# SimpleFOCShield_v3-Redesigned.net
KiCad netlist of a schematic drawn in EasyEDA Pro
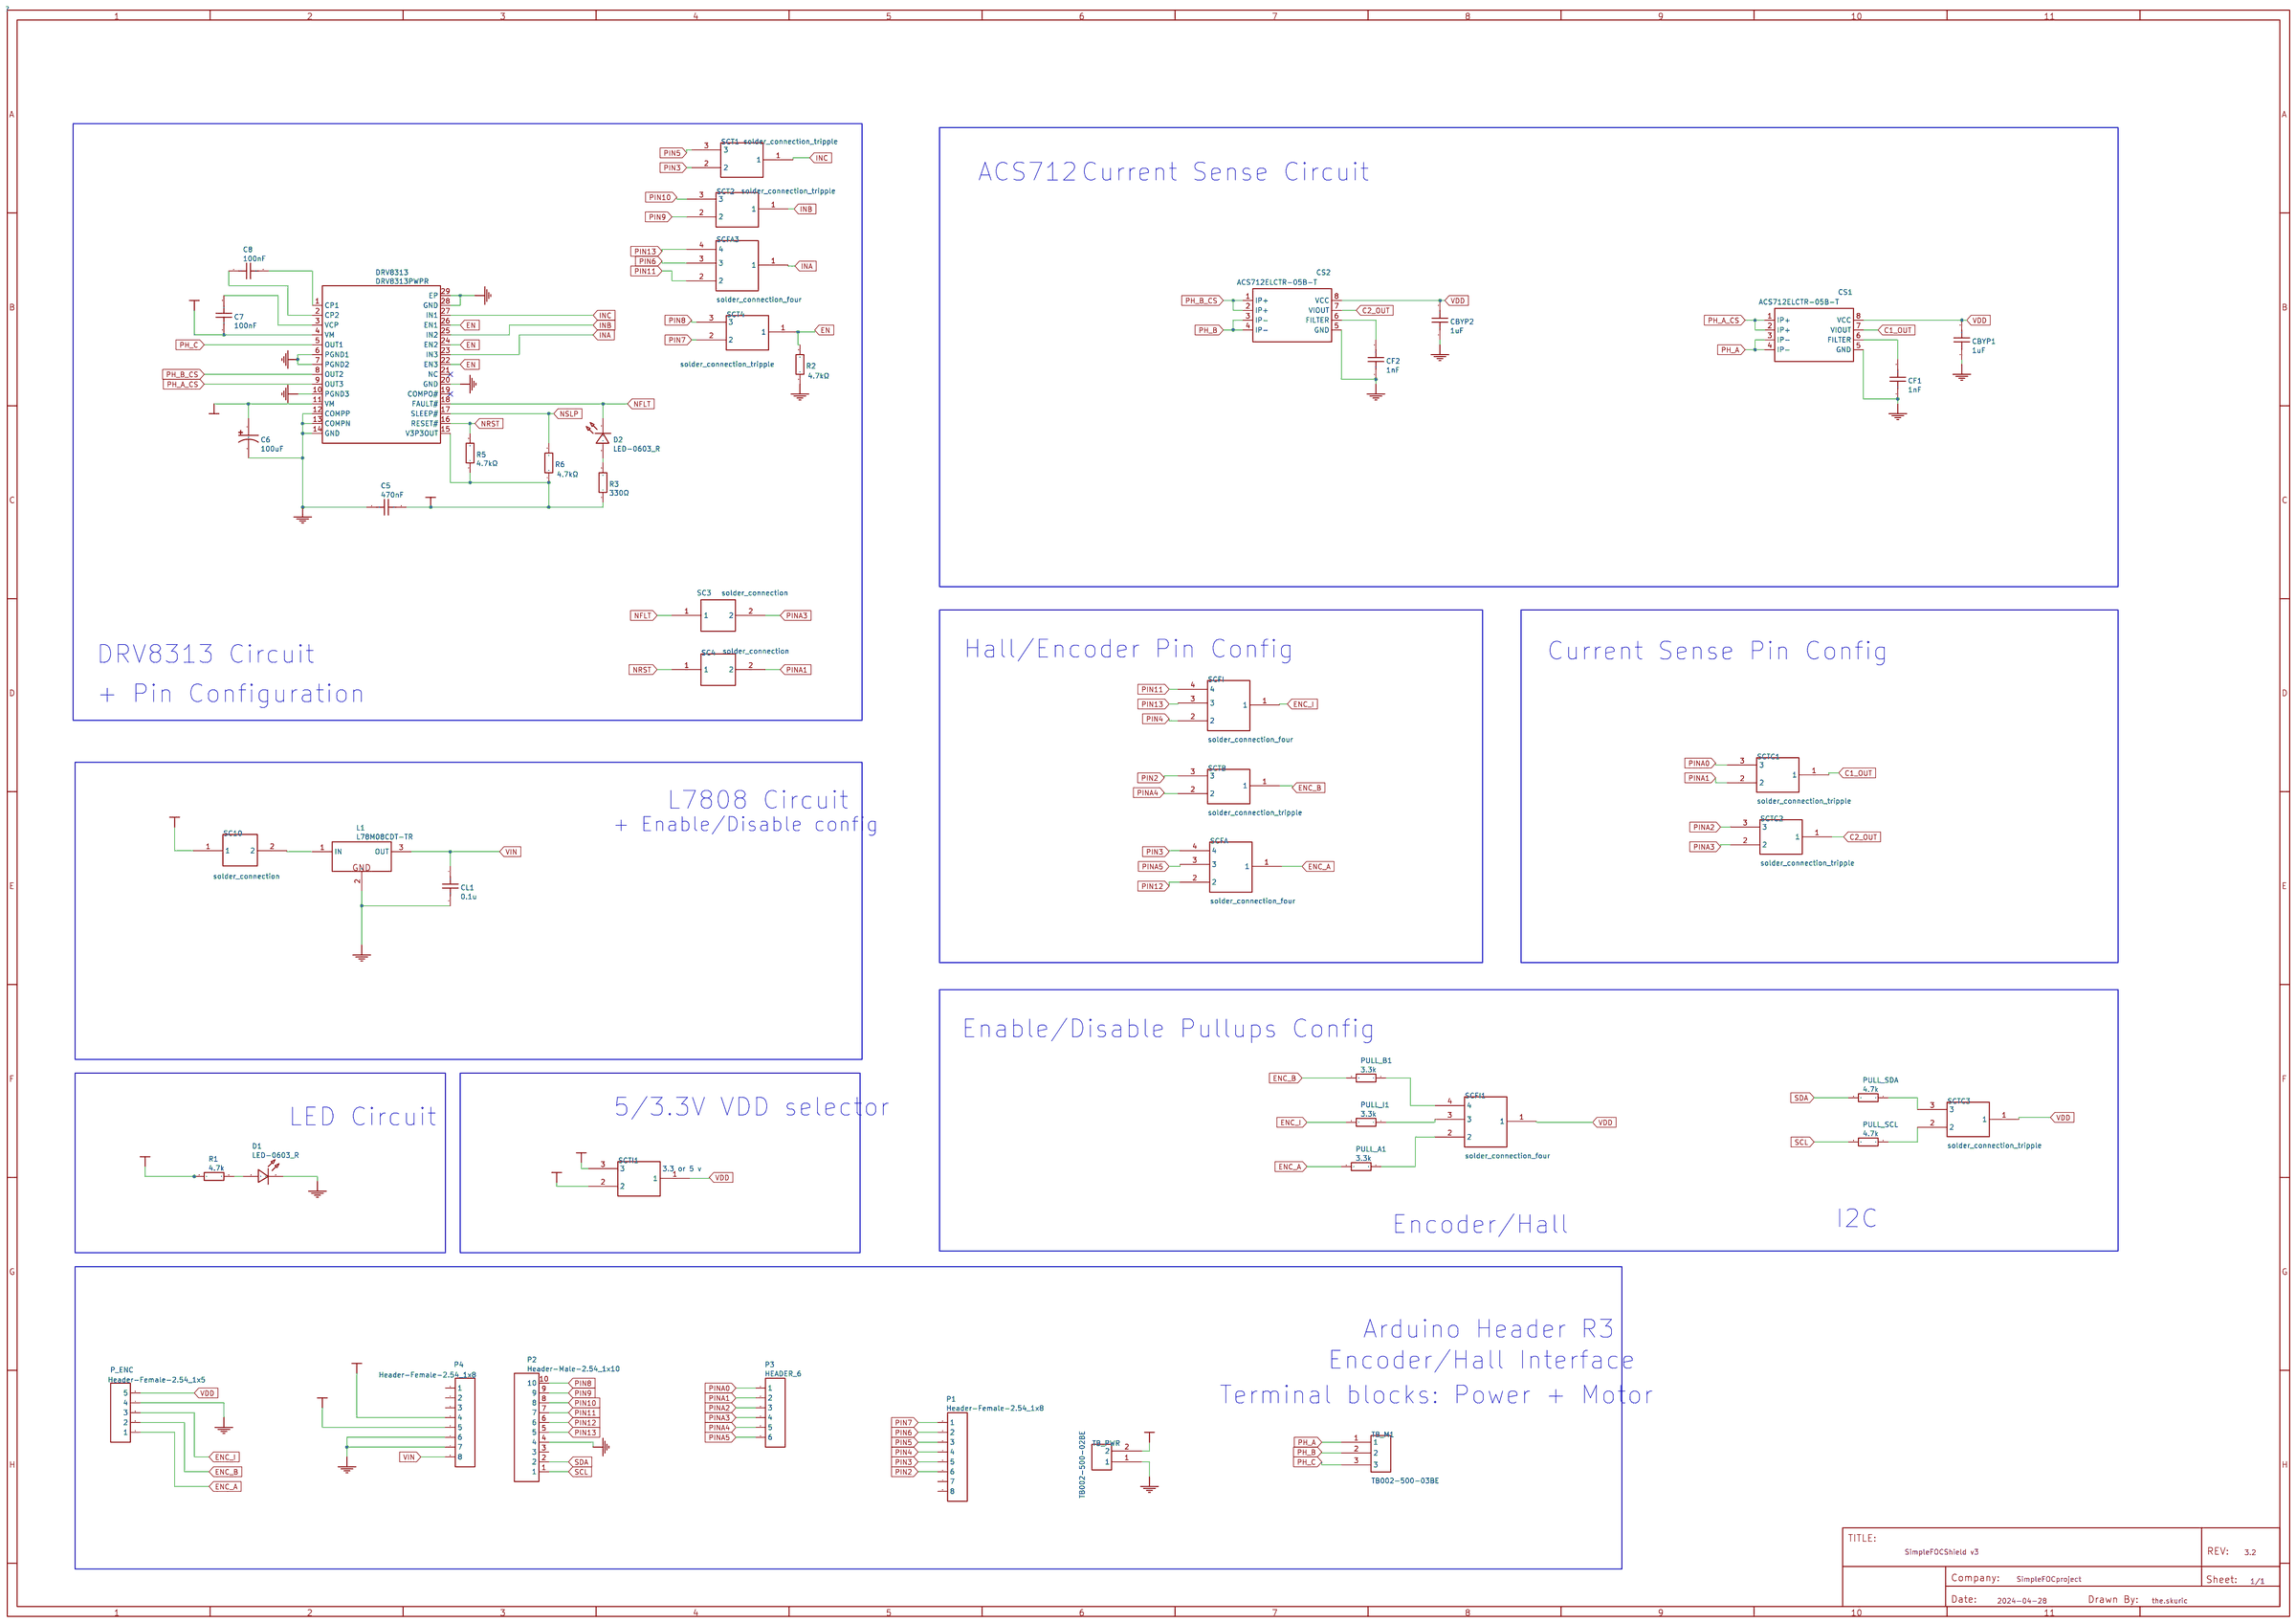
[diagram p0: schematic sheet]

(export (version "E")
  (design (tool "Eeschema 10.0.6"))
  (components
    (comp (ref "C5")
      (value "470nF")
      (footprint "easyedapro:C0603_1")
      (fields (field (name "Manufacturer Part") "CC0603ZRY5V6BB474") (field (name "Manufacturer") "YAGEO"))
      (libsource (lib "easyedapro") (part "470nF"))
    )
    (comp (ref "C6")
      (value "100uF")
      (footprint "easyedapro:CAP-SMD_BD6.3-L6.6-W6.6-FD")
      (fields
        (field (name "Manufacturer Part") "VT1V101M-CRE77")
        (field (name "Manufacturer") "Vertical Technology")
      )
      (libsource (lib "easyedapro") (part "100uF"))
    )
    (comp (ref "C7")
      (value "100nF")
      (footprint "easyedapro:C0603_1")
      (fields (field (name "Manufacturer Part") "CL10B104KB8NNNC") (field (name "Manufacturer") "SAMSUNG"))
      (libsource (lib "easyedapro") (part "100nF"))
    )
    (comp (ref "C8")
      (value "100nF")
      (footprint "easyedapro:C0603_1")
      (fields (field (name "Manufacturer Part") "CL10B104KB8NNNC") (field (name "Manufacturer") "SAMSUNG"))
      (libsource (lib "easyedapro") (part "100nF"))
    )
    (comp (ref "CBYP1")
      (value "1uF")
      (footprint "easyedapro:C0603_1")
      (libsource (lib "easyedapro") (part "1uF"))
    )
    (comp (ref "CBYP2")
      (value "1uF")
      (footprint "easyedapro:C0603_1")
      (libsource (lib "easyedapro") (part "1uF"))
    )
    (comp (ref "CF1")
      (value "1nF")
      (footprint "easyedapro:C0603_1")
      (libsource (lib "easyedapro") (part "1nF"))
    )
    (comp (ref "CF2")
      (value "1nF")
      (footprint "easyedapro:C0603_1")
      (libsource (lib "easyedapro") (part "1nF"))
    )
    (comp (ref "CL1")
      (value "0.1u")
      (footprint "easyedapro:C0603_1")
      (libsource (lib "easyedapro") (part "0.1u"))
    )
    (comp (ref "CS1")
      (value "ACS712ELCTR-05B-T")
      (footprint "easyedapro:SOIC-8_L5.0-W4.0-P1.27-LS6.0-BL")
      (fields (field (name "Manufacturer") "ALLEGRO(美国埃戈罗)"))
      (libsource (lib "easyedapro") (part "ACS712ELCTR-05B-T"))
    )
    (comp (ref "CS2")
      (value "ACS712ELCTR-05B-T")
      (footprint "easyedapro:SOIC-8_L5.0-W4.0-P1.27-LS6.0-BL")
      (fields (field (name "Manufacturer") "ALLEGRO(美国埃戈罗)"))
      (libsource (lib "easyedapro") (part "ACS712ELCTR-05B-T"))
    )
    (comp (ref "D1")
      (value "LED-0603_R")
      (footprint "easyedapro:LED0603_RED")
      (fields
        (field (name "Manufacturer Part") "19-217/R6C-AL1M2VY/3T")
        (field (name "Manufacturer") "EVERLIGHT(台湾亿光)")
      )
      (libsource (lib "easyedapro") (part "LED-0603_R"))
    )
    (comp (ref "D2")
      (value "LED-0603_R")
      (footprint "easyedapro:LED0603_RED")
      (fields
        (field (name "Manufacturer Part") "19-217/R6C-AL1M2VY/3T")
        (field (name "Manufacturer") "EVERLIGHT(台湾亿光)")
      )
      (libsource (lib "easyedapro") (part "LED-0603_R"))
    )
    (comp (ref "DRV8313")
      (value "DRV8313PWPR")
      (footprint "easyedapro:HTSSOP-28_L9.8-W4.5-P0.65-LS6.6-BL-EP")
      (fields (field (name "Manufacturer") "Texas Instruments"))
      (libsource (lib "easyedapro") (part "DRV8313PWPR"))
    )
    (comp (ref "L1")
      (value "L78M08CDT-TR")
      (footprint "easyedapro:TO-252-2_L6.6-W6.1-P4.57-LS9.9-TL-CW")
      (fields (field (name "Manufacturer") "STMicroelectronics"))
      (libsource (lib "easyedapro") (part "L78M08CDT-TR"))
    )
    (comp (ref "P1")
      (value "Header-Female-2.54_1x8")
      (footprint "easyedapro:HDR-TH_8P-P2.54-V-F-1")
      (fields
        (field (name "Manufacturer Part") "Female headerHDR1X8-2.54")
        (field (name "Manufacturer") "BOOMELE")
      )
      (libsource (lib "easyedapro") (part "Header-Female-2.54_1x8"))
    )
    (comp (ref "P2")
      (value "Header-Male-2.54_1x10")
      (footprint "easyedapro:HDR-TH_10P-P2.54-V-M-1")
      (fields (field (name "Manufacturer Part") "Headers  Pins2.54mm1*10P"))
      (libsource (lib "easyedapro") (part "Header-Male-2.54_1x10"))
    )
    (comp (ref "P3")
      (value "HEADER_6")
      (footprint "easyedapro:HDR-M-2.54_1X6")
      (libsource (lib "easyedapro") (part "HEADER_6"))
    )
    (comp (ref "P4")
      (value "Header-Female-2.54_1x8")
      (footprint "easyedapro:HDR-TH_8P-P2.54-V-F-1")
      (fields
        (field (name "Manufacturer Part") "Female headerHDR1X8-2.54")
        (field (name "Manufacturer") "BOOMELE")
      )
      (libsource (lib "easyedapro") (part "Header-Female-2.54_1x8"))
    )
    (comp (ref "PULL_A1")
      (value "3.3k")
      (footprint "easyedapro:R0603_1")
      (libsource (lib "easyedapro") (part "3.3k"))
    )
    (comp (ref "PULL_B1")
      (value "3.3k")
      (footprint "easyedapro:R0603_1")
      (libsource (lib "easyedapro") (part "3.3k"))
    )
    (comp (ref "PULL_I1")
      (value "3.3k")
      (footprint "easyedapro:R0603_1")
      (libsource (lib "easyedapro") (part "3.3k"))
    )
    (comp (ref "PULL_SCL")
      (value "4.7k")
      (footprint "easyedapro:R0603_1")
      (fields (field (name "Manufacturer Part") "0603WAF4701T5E") (field (name "Manufacturer") "UniOhm"))
      (libsource (lib "easyedapro") (part "4.7k"))
    )
    (comp (ref "PULL_SDA")
      (value "4.7k")
      (footprint "easyedapro:R0603_1")
      (fields (field (name "Manufacturer Part") "0603WAF4701T5E") (field (name "Manufacturer") "UniOhm"))
      (libsource (lib "easyedapro") (part "4.7k"))
    )
    (comp (ref "P_ENC")
      (value "Header-Female-2.54_1x5")
      (footprint "easyedapro:HDR-TH_5P-P2.54-V-F")
      (fields
        (field (name "Manufacturer Part") "2.54mm 1*5p Female header")
        (field (name "Manufacturer") "BOOMELE")
      )
      (libsource (lib "easyedapro") (part "Header-Female-2.54_1x5"))
    )
    (comp (ref "R1")
      (value "4.7k")
      (footprint "easyedapro:R0603_1")
      (fields (field (name "Manufacturer Part") "0603WAF4701T5E") (field (name "Manufacturer") "UniOhm"))
      (libsource (lib "easyedapro") (part "4.7k"))
    )
    (comp (ref "R2")
      (value "4.7kΩ")
      (footprint "easyedapro:R0603_1")
      (fields (field (name "Manufacturer Part") "0603WAF4701T5E") (field (name "Manufacturer") "UniOhm"))
      (libsource (lib "easyedapro") (part "4.7kΩ"))
    )
    (comp (ref "R3")
      (value "330Ω")
      (footprint "easyedapro:R0603_1")
      (libsource (lib "easyedapro") (part "330Ω"))
    )
    (comp (ref "R5")
      (value "4.7kΩ")
      (footprint "easyedapro:R0603_1")
      (fields (field (name "Manufacturer Part") "0603WAF4701T5E") (field (name "Manufacturer") "UniOhm"))
      (libsource (lib "easyedapro") (part "4.7kΩ"))
    )
    (comp (ref "R6")
      (value "4.7kΩ")
      (footprint "easyedapro:R0603_1")
      (fields (field (name "Manufacturer Part") "0603WAF4701T5E") (field (name "Manufacturer") "UniOhm"))
      (libsource (lib "easyedapro") (part "4.7kΩ"))
    )
    (comp (ref "SC3")
      (value "solder_connection")
      (footprint "easyedapro:SOLDER_CONNECTION")
      (libsource (lib "easyedapro") (part "solder_connection"))
    )
    (comp (ref "SC4")
      (value "solder_connection")
      (footprint "easyedapro:SOLDER_CONNECTION")
      (libsource (lib "easyedapro") (part "solder_connection"))
    )
    (comp (ref "SC10")
      (value "solder_connection")
      (footprint "easyedapro:SOLDER_CONNECTION")
      (libsource (lib "") (part "solder_connection_1"))
    )
    (comp (ref "SCFA")
      (value "solder_connection_four")
      (footprint "easyedapro:SOLDER_CONNECTION_FOUR")
      (libsource (lib "") (part "solder_connection_four_1"))
    )
    (comp (ref "SCFA3")
      (value "solder_connection_four")
      (footprint "easyedapro:SOLDER_CONNECTION_FOUR")
      (libsource (lib "") (part "solder_connection_four_2"))
    )
    (comp (ref "SCFI")
      (value "solder_connection_four")
      (footprint "easyedapro:SOLDER_CONNECTION_FOUR")
      (libsource (lib "easyedapro") (part "solder_connection_four"))
    )
    (comp (ref "SCFI1")
      (value "solder_connection_four")
      (footprint "easyedapro:SOLDER_CONNECTION_FOUR")
      (libsource (lib "easyedapro") (part "solder_connection_four"))
    )
    (comp (ref "SCT1")
      (value "solder_connection_tripple")
      (footprint "easyedapro:SOLDER_CONNECTION_TRIPPLE")
      (libsource (lib "") (part "solder_connection_tripple_5"))
    )
    (comp (ref "SCT2")
      (value "solder_connection_tripple")
      (footprint "easyedapro:SOLDER_CONNECTION_TRIPPLE")
      (libsource (lib "") (part "solder_connection_tripple_1"))
    )
    (comp (ref "SCT4")
      (value "solder_connection_tripple")
      (footprint "easyedapro:SOLDER_CONNECTION_TRIPPLE")
      (libsource (lib "") (part "solder_connection_tripple_4"))
    )
    (comp (ref "SCTB")
      (value "solder_connection_tripple")
      (footprint "easyedapro:SOLDER_CONNECTION_TRIPPLE")
      (libsource (lib "") (part "solder_connection_tripple_3"))
    )
    (comp (ref "SCTC1")
      (value "solder_connection_tripple")
      (footprint "easyedapro:SOLDER_CONNECTION_TRIPPLE")
      (libsource (lib "") (part "solder_connection_tripple_2"))
    )
    (comp (ref "SCTC2")
      (value "solder_connection_tripple")
      (footprint "easyedapro:SOLDER_CONNECTION_TRIPPLE")
      (libsource (lib "easyedapro") (part "solder_connection_tripple"))
    )
    (comp (ref "SCTC3")
      (value "solder_connection_tripple")
      (footprint "easyedapro:SOLDER_CONNECTION_TRIPPLE")
      (libsource (lib "easyedapro") (part "solder_connection_tripple"))
    )
    (comp (ref "SCTI1")
      (value "3.3 or 5 v")
      (footprint "easyedapro:SOLDER_CONNECTION_TRIPPLE")
      (libsource (lib "easyedapro") (part "3.3 or 5 v"))
    )
    (comp (ref "TB_M1")
      (value "TB002-500-03BE")
      (footprint "easyedapro:TB002-500-03BE")
      (libsource (lib "easyedapro") (part "TB002-500-03BE"))
    )
    (comp (ref "TB_PWR")
      (value "TB002-500-02BE")
      (footprint "easyedapro:TB002-500-02BE")
      (libsource (lib "easyedapro") (part "TB002-500-02BE"))
    )
  )
  (nets
    (net (code "1") (name "+5V") (class "Default")
      (node (ref "P4") (pin "5") (pinfunction "5_5") (pintype "input"))
      (node (ref "SCTI1") (pin "2") (pinfunction "2_2") (pintype "unspecified"))
    )
    (net (code "2") (name "3.3V") (class "Default")
      (node (ref "C5") (pin "2") (pinfunction "2_2") (pintype "unspecified"))
      (node (ref "DRV8313") (pin "15") (pinfunction "V3P3OUT_15") (pintype "unspecified"))
      (node (ref "R3") (pin "1") (pinfunction "1_1") (pintype "input"))
      (node (ref "R5") (pin "1") (pinfunction "1_1") (pintype "input"))
      (node (ref "R6") (pin "1") (pinfunction "1_1") (pintype "input"))
    )
    (net (code "3") (name "C1_OUT") (class "Default")
      (node (ref "CS1") (pin "7") (pinfunction "VIOUT_7") (pintype "unspecified"))
      (node (ref "SCTC1") (pin "1") (pinfunction "1_1") (pintype "unspecified"))
    )
    (net (code "4") (name "C2_OUT") (class "Default")
      (node (ref "CS2") (pin "7") (pinfunction "VIOUT_7") (pintype "unspecified"))
      (node (ref "SCTC2") (pin "1") (pinfunction "1_1") (pintype "unspecified"))
    )
    (net (code "5") (name "EN") (class "Default")
      (node (ref "DRV8313") (pin "22") (pinfunction "EN3_22") (pintype "unspecified"))
      (node (ref "DRV8313") (pin "24") (pinfunction "EN2_24") (pintype "unspecified"))
      (node (ref "DRV8313") (pin "26") (pinfunction "EN1_26") (pintype "unspecified"))
      (node (ref "R2") (pin "2") (pinfunction "2_2") (pintype "input"))
      (node (ref "SCT4") (pin "1") (pinfunction "1_1") (pintype "unspecified"))
    )
    (net (code "6") (name "ENC_A") (class "Default")
      (node (ref "PULL_A1") (pin "2") (pinfunction "2_2") (pintype "input"))
      (node (ref "P_ENC") (pin "1") (pinfunction "1_1") (pintype "input"))
      (node (ref "SCFA") (pin "1") (pinfunction "1_1") (pintype "unspecified"))
    )
    (net (code "7") (name "ENC_B") (class "Default")
      (node (ref "PULL_B1") (pin "2") (pinfunction "2_2") (pintype "input"))
      (node (ref "P_ENC") (pin "2") (pinfunction "2_2") (pintype "input"))
      (node (ref "SCTB") (pin "1") (pinfunction "1_1") (pintype "unspecified"))
    )
    (net (code "8") (name "ENC_I") (class "Default")
      (node (ref "PULL_I1") (pin "2") (pinfunction "2_2") (pintype "input"))
      (node (ref "P_ENC") (pin "3") (pinfunction "3_3") (pintype "input"))
      (node (ref "SCFI") (pin "1") (pinfunction "1_1") (pintype "unspecified"))
    )
    (net (code "9") (name "GND") (class "Default")
      (node (ref "C5") (pin "1") (pinfunction "1_1") (pintype "unspecified"))
      (node (ref "C6") (pin "2") (pinfunction "2_2") (pintype "unspecified"))
      (node (ref "CBYP1") (pin "1") (pinfunction "1_1") (pintype "unspecified"))
      (node (ref "CBYP2") (pin "1") (pinfunction "1_1") (pintype "unspecified"))
      (node (ref "CF1") (pin "1") (pinfunction "1_1") (pintype "unspecified"))
      (node (ref "CF2") (pin "1") (pinfunction "1_1") (pintype "unspecified"))
      (node (ref "CL1") (pin "2") (pinfunction "2_2") (pintype "unspecified"))
      (node (ref "CS1") (pin "5") (pinfunction "GND_5") (pintype "unspecified"))
      (node (ref "CS2") (pin "5") (pinfunction "GND_5") (pintype "unspecified"))
      (node (ref "D1") (pin "2") (pinfunction "2_2") (pintype "unspecified"))
      (node (ref "DRV8313") (pin "10") (pinfunction "PGND3_10") (pintype "unspecified"))
      (node (ref "DRV8313") (pin "12") (pinfunction "COMPP_12") (pintype "unspecified"))
      (node (ref "DRV8313") (pin "13") (pinfunction "COMPN_13") (pintype "unspecified"))
      (node (ref "DRV8313") (pin "14") (pinfunction "GND_14") (pintype "unspecified"))
      (node (ref "DRV8313") (pin "20") (pinfunction "GND_20") (pintype "unspecified"))
      (node (ref "DRV8313") (pin "28") (pinfunction "GND_28") (pintype "unspecified"))
      (node (ref "DRV8313") (pin "29") (pinfunction "EP_29") (pintype "unspecified"))
      (node (ref "DRV8313") (pin "6") (pinfunction "PGND1_6") (pintype "unspecified"))
      (node (ref "DRV8313") (pin "7") (pinfunction "PGND2_7") (pintype "unspecified"))
      (node (ref "L1") (pin "2") (pinfunction "GND_2") (pintype "unspecified"))
      (node (ref "P2") (pin "4") (pinfunction "4_4") (pintype "unspecified"))
      (node (ref "P4") (pin "6") (pinfunction "6_6") (pintype "input"))
      (node (ref "P4") (pin "7") (pinfunction "7_7") (pintype "input"))
      (node (ref "P_ENC") (pin "4") (pinfunction "4_4") (pintype "input"))
      (node (ref "R2") (pin "1") (pinfunction "1_1") (pintype "input"))
      (node (ref "TB_PWR") (pin "1") (pinfunction "1_1") (pintype "unspecified"))
    )
    (net (code "10") (name "INA") (class "Default")
      (node (ref "DRV8313") (pin "23") (pinfunction "IN3_23") (pintype "unspecified"))
      (node (ref "SCFA3") (pin "1") (pinfunction "1_1") (pintype "unspecified"))
    )
    (net (code "11") (name "INB") (class "Default")
      (node (ref "DRV8313") (pin "25") (pinfunction "IN2_25") (pintype "unspecified"))
      (node (ref "SCT2") (pin "1") (pinfunction "1_1") (pintype "unspecified"))
    )
    (net (code "12") (name "INC") (class "Default")
      (node (ref "DRV8313") (pin "27") (pinfunction "IN1_27") (pintype "unspecified"))
      (node (ref "SCT1") (pin "1") (pinfunction "1_1") (pintype "unspecified"))
    )
    (net (code "13") (name "NFLT") (class "Default")
      (node (ref "D2") (pin "2") (pinfunction "2_2") (pintype "unspecified"))
      (node (ref "DRV8313") (pin "18") (pinfunction "FAULT#_18") (pintype "unspecified"))
      (node (ref "SC3") (pin "1") (pinfunction "1_1") (pintype "unspecified"))
    )
    (net (code "14") (name "NRST") (class "Default")
      (node (ref "DRV8313") (pin "16") (pinfunction "RESET#_16") (pintype "unspecified"))
      (node (ref "R5") (pin "2") (pinfunction "2_2") (pintype "input"))
      (node (ref "SC4") (pin "1") (pinfunction "1_1") (pintype "unspecified"))
    )
    (net (code "15") (name "NSLP") (class "Default")
      (node (ref "DRV8313") (pin "17") (pinfunction "SLEEP#_17") (pintype "unspecified"))
      (node (ref "R6") (pin "2") (pinfunction "2_2") (pintype "input"))
    )
    (net (code "16") (name "Net-(CS1-FILTER)") (class "Default")
      (node (ref "CF1") (pin "2") (pinfunction "2_2") (pintype "unspecified"))
      (node (ref "CS1") (pin "6") (pinfunction "FILTER_6") (pintype "unspecified"))
    )
    (net (code "17") (name "Net-(CS2-FILTER)") (class "Default")
      (node (ref "CF2") (pin "2") (pinfunction "2_2") (pintype "unspecified"))
      (node (ref "CS2") (pin "6") (pinfunction "FILTER_6") (pintype "unspecified"))
    )
    (net (code "18") (name "Net-(D1-Pad1)") (class "Default")
      (node (ref "D1") (pin "1") (pinfunction "1_1") (pintype "unspecified"))
      (node (ref "R1") (pin "1") (pinfunction "1_1") (pintype "input"))
    )
    (net (code "19") (name "Net-(D2-Pad1)") (class "Default")
      (node (ref "D2") (pin "1") (pinfunction "1_1") (pintype "unspecified"))
      (node (ref "R3") (pin "2") (pinfunction "2_2") (pintype "input"))
    )
    (net (code "20") (name "Net-(DRV8313-CP1)") (class "Default")
      (node (ref "C8") (pin "2") (pinfunction "2_2") (pintype "unspecified"))
      (node (ref "DRV8313") (pin "1") (pinfunction "CP1_1") (pintype "unspecified"))
    )
    (net (code "21") (name "Net-(DRV8313-CP2)") (class "Default")
      (node (ref "C8") (pin "1") (pinfunction "1_1") (pintype "unspecified"))
      (node (ref "DRV8313") (pin "2") (pinfunction "CP2_2") (pintype "unspecified"))
    )
    (net (code "22") (name "Net-(DRV8313-VCP)") (class "Default")
      (node (ref "C7") (pin "2") (pinfunction "2_2") (pintype "unspecified"))
      (node (ref "DRV8313") (pin "3") (pinfunction "VCP_3") (pintype "unspecified"))
    )
    (net (code "23") (name "Net-(L1-IN)") (class "Default")
      (node (ref "L1") (pin "1") (pinfunction "IN_1") (pintype "unspecified"))
      (node (ref "SC10") (pin "2") (pinfunction "2_2") (pintype "unspecified"))
    )
    (net (code "24") (name "Net-(PULL_A1-Pad1)") (class "Default")
      (node (ref "PULL_A1") (pin "1") (pinfunction "1_1") (pintype "input"))
      (node (ref "SCFI1") (pin "2") (pinfunction "2_2") (pintype "unspecified"))
    )
    (net (code "25") (name "Net-(PULL_B1-Pad1)") (class "Default")
      (node (ref "PULL_B1") (pin "1") (pinfunction "1_1") (pintype "input"))
      (node (ref "SCFI1") (pin "4") (pinfunction "4_4") (pintype "unspecified"))
    )
    (net (code "26") (name "Net-(PULL_I1-Pad1)") (class "Default")
      (node (ref "PULL_I1") (pin "1") (pinfunction "1_1") (pintype "input"))
      (node (ref "SCFI1") (pin "3") (pinfunction "3_3") (pintype "unspecified"))
    )
    (net (code "27") (name "Net-(PULL_SCL-Pad1)") (class "Default")
      (node (ref "PULL_SCL") (pin "1") (pinfunction "1_1") (pintype "input"))
      (node (ref "SCTC3") (pin "2") (pinfunction "2_2") (pintype "unspecified"))
    )
    (net (code "28") (name "Net-(PULL_SDA-Pad1)") (class "Default")
      (node (ref "PULL_SDA") (pin "1") (pinfunction "1_1") (pintype "input"))
      (node (ref "SCTC3") (pin "3") (pinfunction "3_3") (pintype "unspecified"))
    )
    (net (code "29") (name "P3.3V") (class "Default")
      (node (ref "P4") (pin "4") (pinfunction "4_4") (pintype "input"))
      (node (ref "SCTI1") (pin "3") (pinfunction "3_3") (pintype "unspecified"))
    )
    (net (code "30") (name "PH_A") (class "Default")
      (node (ref "CS1") (pin "3") (pinfunction "IP-_3") (pintype "unspecified"))
      (node (ref "CS1") (pin "4") (pinfunction "IP-_4") (pintype "unspecified"))
      (node (ref "TB_M1") (pin "1") (pinfunction "1_1") (pintype "unspecified"))
    )
    (net (code "31") (name "PH_A_CS") (class "Default")
      (node (ref "CS1") (pin "1") (pinfunction "IP+_1") (pintype "unspecified"))
      (node (ref "CS1") (pin "2") (pinfunction "IP+_2") (pintype "unspecified"))
      (node (ref "DRV8313") (pin "9") (pinfunction "OUT3_9") (pintype "unspecified"))
    )
    (net (code "32") (name "PH_B") (class "Default")
      (node (ref "CS2") (pin "3") (pinfunction "IP-_3") (pintype "unspecified"))
      (node (ref "CS2") (pin "4") (pinfunction "IP-_4") (pintype "unspecified"))
      (node (ref "TB_M1") (pin "2") (pinfunction "2_2") (pintype "unspecified"))
    )
    (net (code "33") (name "PH_B_CS") (class "Default")
      (node (ref "CS2") (pin "1") (pinfunction "IP+_1") (pintype "unspecified"))
      (node (ref "CS2") (pin "2") (pinfunction "IP+_2") (pintype "unspecified"))
      (node (ref "DRV8313") (pin "8") (pinfunction "OUT2_8") (pintype "unspecified"))
    )
    (net (code "34") (name "PH_C") (class "Default")
      (node (ref "DRV8313") (pin "5") (pinfunction "OUT1_5") (pintype "unspecified"))
      (node (ref "TB_M1") (pin "3") (pinfunction "3_3") (pintype "unspecified"))
    )
    (net (code "35") (name "PIN2") (class "Default")
      (node (ref "P1") (pin "6") (pinfunction "6_6") (pintype "input"))
      (node (ref "SCTB") (pin "3") (pinfunction "3_3") (pintype "unspecified"))
    )
    (net (code "36") (name "PIN3") (class "Default")
      (node (ref "P1") (pin "5") (pinfunction "5_5") (pintype "input"))
      (node (ref "SCFA") (pin "4") (pinfunction "4_4") (pintype "unspecified"))
      (node (ref "SCT1") (pin "2") (pinfunction "2_2") (pintype "unspecified"))
    )
    (net (code "37") (name "PIN4") (class "Default")
      (node (ref "P1") (pin "4") (pinfunction "4_4") (pintype "input"))
      (node (ref "SCFI") (pin "2") (pinfunction "2_2") (pintype "unspecified"))
    )
    (net (code "38") (name "PIN5") (class "Default")
      (node (ref "P1") (pin "3") (pinfunction "3_3") (pintype "input"))
      (node (ref "SCT1") (pin "3") (pinfunction "3_3") (pintype "unspecified"))
    )
    (net (code "39") (name "PIN6") (class "Default")
      (node (ref "P1") (pin "2") (pinfunction "2_2") (pintype "input"))
      (node (ref "SCFA3") (pin "3") (pinfunction "3_3") (pintype "unspecified"))
    )
    (net (code "40") (name "PIN7") (class "Default")
      (node (ref "P1") (pin "1") (pinfunction "1_1") (pintype "input"))
      (node (ref "SCT4") (pin "2") (pinfunction "2_2") (pintype "unspecified"))
    )
    (net (code "41") (name "PIN8") (class "Default")
      (node (ref "P2") (pin "10") (pinfunction "10_10") (pintype "unspecified"))
      (node (ref "SCT4") (pin "3") (pinfunction "3_3") (pintype "unspecified"))
    )
    (net (code "42") (name "PIN9") (class "Default")
      (node (ref "P2") (pin "9") (pinfunction "9_9") (pintype "unspecified"))
      (node (ref "SCT2") (pin "2") (pinfunction "2_2") (pintype "unspecified"))
    )
    (net (code "43") (name "PIN10") (class "Default")
      (node (ref "P2") (pin "8") (pinfunction "8_8") (pintype "unspecified"))
      (node (ref "SCT2") (pin "3") (pinfunction "3_3") (pintype "unspecified"))
    )
    (net (code "44") (name "PIN11") (class "Default")
      (node (ref "P2") (pin "7") (pinfunction "7_7") (pintype "unspecified"))
      (node (ref "SCFA3") (pin "2") (pinfunction "2_2") (pintype "unspecified"))
      (node (ref "SCFI") (pin "4") (pinfunction "4_4") (pintype "unspecified"))
    )
    (net (code "45") (name "PIN12") (class "Default")
      (node (ref "P2") (pin "6") (pinfunction "6_6") (pintype "unspecified"))
      (node (ref "SCFA") (pin "2") (pinfunction "2_2") (pintype "unspecified"))
    )
    (net (code "46") (name "PIN13") (class "Default")
      (node (ref "P2") (pin "5") (pinfunction "5_5") (pintype "unspecified"))
      (node (ref "SCFA3") (pin "4") (pinfunction "4_4") (pintype "unspecified"))
      (node (ref "SCFI") (pin "3") (pinfunction "3_3") (pintype "unspecified"))
    )
    (net (code "47") (name "PINA0") (class "Default")
      (node (ref "P3") (pin "1") (pinfunction "1_1") (pintype "input"))
      (node (ref "SCTC1") (pin "3") (pinfunction "3_3") (pintype "unspecified"))
    )
    (net (code "48") (name "PINA1") (class "Default")
      (node (ref "P3") (pin "2") (pinfunction "2_2") (pintype "input"))
      (node (ref "SC4") (pin "2") (pinfunction "2_2") (pintype "unspecified"))
      (node (ref "SCTC1") (pin "2") (pinfunction "2_2") (pintype "unspecified"))
    )
    (net (code "49") (name "PINA2") (class "Default")
      (node (ref "P3") (pin "3") (pinfunction "3_3") (pintype "input"))
      (node (ref "SCTC2") (pin "3") (pinfunction "3_3") (pintype "unspecified"))
    )
    (net (code "50") (name "PINA3") (class "Default")
      (node (ref "P3") (pin "4") (pinfunction "4_4") (pintype "input"))
      (node (ref "SC3") (pin "2") (pinfunction "2_2") (pintype "unspecified"))
      (node (ref "SCTC2") (pin "2") (pinfunction "2_2") (pintype "unspecified"))
    )
    (net (code "51") (name "PINA4") (class "Default")
      (node (ref "P3") (pin "5") (pinfunction "5_5") (pintype "input"))
      (node (ref "SCTB") (pin "2") (pinfunction "2_2") (pintype "unspecified"))
    )
    (net (code "52") (name "PINA5") (class "Default")
      (node (ref "P3") (pin "6") (pinfunction "6_6") (pintype "input"))
      (node (ref "SCFA") (pin "3") (pinfunction "3_3") (pintype "unspecified"))
    )
    (net (code "53") (name "SCL") (class "Default")
      (node (ref "P2") (pin "1") (pinfunction "1_1") (pintype "unspecified"))
      (node (ref "PULL_SCL") (pin "2") (pinfunction "2_2") (pintype "input"))
    )
    (net (code "54") (name "SDA") (class "Default")
      (node (ref "P2") (pin "2") (pinfunction "2_2") (pintype "unspecified"))
      (node (ref "PULL_SDA") (pin "2") (pinfunction "2_2") (pintype "input"))
    )
    (net (code "55") (name "VCC") (class "Default")
      (node (ref "C6") (pin "1") (pinfunction "1_1") (pintype "unspecified"))
      (node (ref "C7") (pin "1") (pinfunction "1_1") (pintype "unspecified"))
      (node (ref "DRV8313") (pin "11") (pinfunction "VM_11") (pintype "unspecified"))
      (node (ref "DRV8313") (pin "4") (pinfunction "VM_4") (pintype "unspecified"))
      (node (ref "R1") (pin "2") (pinfunction "2_2") (pintype "input"))
      (node (ref "SC10") (pin "1") (pinfunction "1_1") (pintype "unspecified"))
      (node (ref "TB_PWR") (pin "2") (pinfunction "2_2") (pintype "unspecified"))
    )
    (net (code "56") (name "VDD") (class "Default")
      (node (ref "CBYP1") (pin "2") (pinfunction "2_2") (pintype "unspecified"))
      (node (ref "CBYP2") (pin "2") (pinfunction "2_2") (pintype "unspecified"))
      (node (ref "CS1") (pin "8") (pinfunction "VCC_8") (pintype "unspecified"))
      (node (ref "CS2") (pin "8") (pinfunction "VCC_8") (pintype "unspecified"))
      (node (ref "P_ENC") (pin "5") (pinfunction "5_5") (pintype "input"))
      (node (ref "SCFI1") (pin "1") (pinfunction "1_1") (pintype "unspecified"))
      (node (ref "SCTC3") (pin "1") (pinfunction "1_1") (pintype "unspecified"))
      (node (ref "SCTI1") (pin "1") (pinfunction "1_1") (pintype "unspecified"))
    )
    (net (code "57") (name "VIN") (class "Default")
      (node (ref "CL1") (pin "1") (pinfunction "1_1") (pintype "unspecified"))
      (node (ref "L1") (pin "3") (pinfunction "OUT_3") (pintype "unspecified"))
      (node (ref "P4") (pin "8") (pinfunction "8_8") (pintype "input"))
    )
    (net (code "58") (name "unconnected-(DRV8313-COMPO#-Pad19)") (class "Default")
      (node (ref "DRV8313") (pin "19") (pinfunction "COMPO#_19") (pintype "unspecified+no_connect"))
    )
    (net (code "59") (name "unconnected-(DRV8313-NC-Pad21)") (class "Default")
      (node (ref "DRV8313") (pin "21") (pinfunction "NC_21") (pintype "unspecified+no_connect"))
    )
    (net (code "60") (name "unconnected-(P1-Pad7)") (class "Default")
      (node (ref "P1") (pin "7") (pinfunction "7_7") (pintype "input"))
    )
    (net (code "61") (name "unconnected-(P1-Pad8)") (class "Default")
      (node (ref "P1") (pin "8") (pinfunction "8_8") (pintype "input"))
    )
    (net (code "62") (name "unconnected-(P2-Pad3)") (class "Default")
      (node (ref "P2") (pin "3") (pinfunction "3_3") (pintype "unspecified"))
    )
    (net (code "63") (name "unconnected-(P4-Pad1)") (class "Default")
      (node (ref "P4") (pin "1") (pinfunction "1_1") (pintype "input"))
    )
    (net (code "64") (name "unconnected-(P4-Pad2)") (class "Default")
      (node (ref "P4") (pin "2") (pinfunction "2_2") (pintype "input"))
    )
    (net (code "65") (name "unconnected-(P4-Pad3)") (class "Default")
      (node (ref "P4") (pin "3") (pinfunction "3_3") (pintype "input"))
    )
  )
)
